# handle.net
KiCad netlist of a schematic drawn in EAGLE
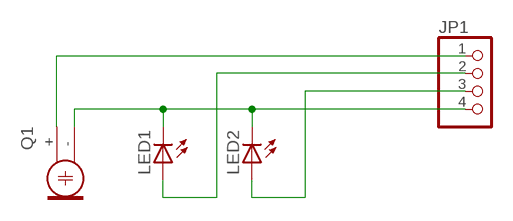
[diagram p0: schematic, sheet 1]

(export (version "E")
  (design (tool "Eeschema 10.0.6"))
  (components
    (comp (ref "JP1")
      (value "PINHD-1X4")
      (footprint "eagle-import:1X04")
      (libsource (lib "eagle-import") (part "PINHD-1X4"))
    )
    (comp (ref "LED1")
      (value "LED5MM")
      (footprint "eagle-import:LED5MM")
      (libsource (lib "eagle-import") (part "LED5MM"))
    )
    (comp (ref "LED2")
      (value "LED5MM")
      (footprint "eagle-import:LED5MM")
      (libsource (lib "eagle-import") (part "LED5MM"))
    )
    (comp (ref "Q1")
      (value "ELECTRET")
      (footprint "eagle-import:9.7ELECTRET")
      (libsource (lib "eagle-import") (part "ELECTRET"))
    )
  )
  (nets
    (net (code "1") (name "Net-(JP1-Pad2)") (class "Default")
      (node (ref "JP1") (pin "2") (pinfunction "2_2") (pintype "passive"))
      (node (ref "LED1") (pin "A") (pinfunction "A_A") (pintype "passive"))
    )
    (net (code "2") (name "Net-(JP1-Pad3)") (class "Default")
      (node (ref "JP1") (pin "3") (pinfunction "3_3") (pintype "passive"))
      (node (ref "LED2") (pin "A") (pinfunction "A_A") (pintype "passive"))
    )
    (net (code "3") (name "Net-(LED1-C)") (class "Default")
      (node (ref "JP1") (pin "4") (pinfunction "4_4") (pintype "passive"))
      (node (ref "LED1") (pin "K") (pinfunction "C_K") (pintype "passive"))
      (node (ref "LED2") (pin "K") (pinfunction "C_K") (pintype "passive"))
      (node (ref "Q1") (pin "-") (pinfunction "1_-") (pintype "passive"))
    )
    (net (code "4") (name "Net-(Q1-2)") (class "Default")
      (node (ref "JP1") (pin "1") (pinfunction "1_1") (pintype "passive"))
      (node (ref "Q1") (pin "+") (pinfunction "2_+") (pintype "passive"))
    )
  )
)
